# side.net
KiCad netlist of a schematic drawn in EAGLE
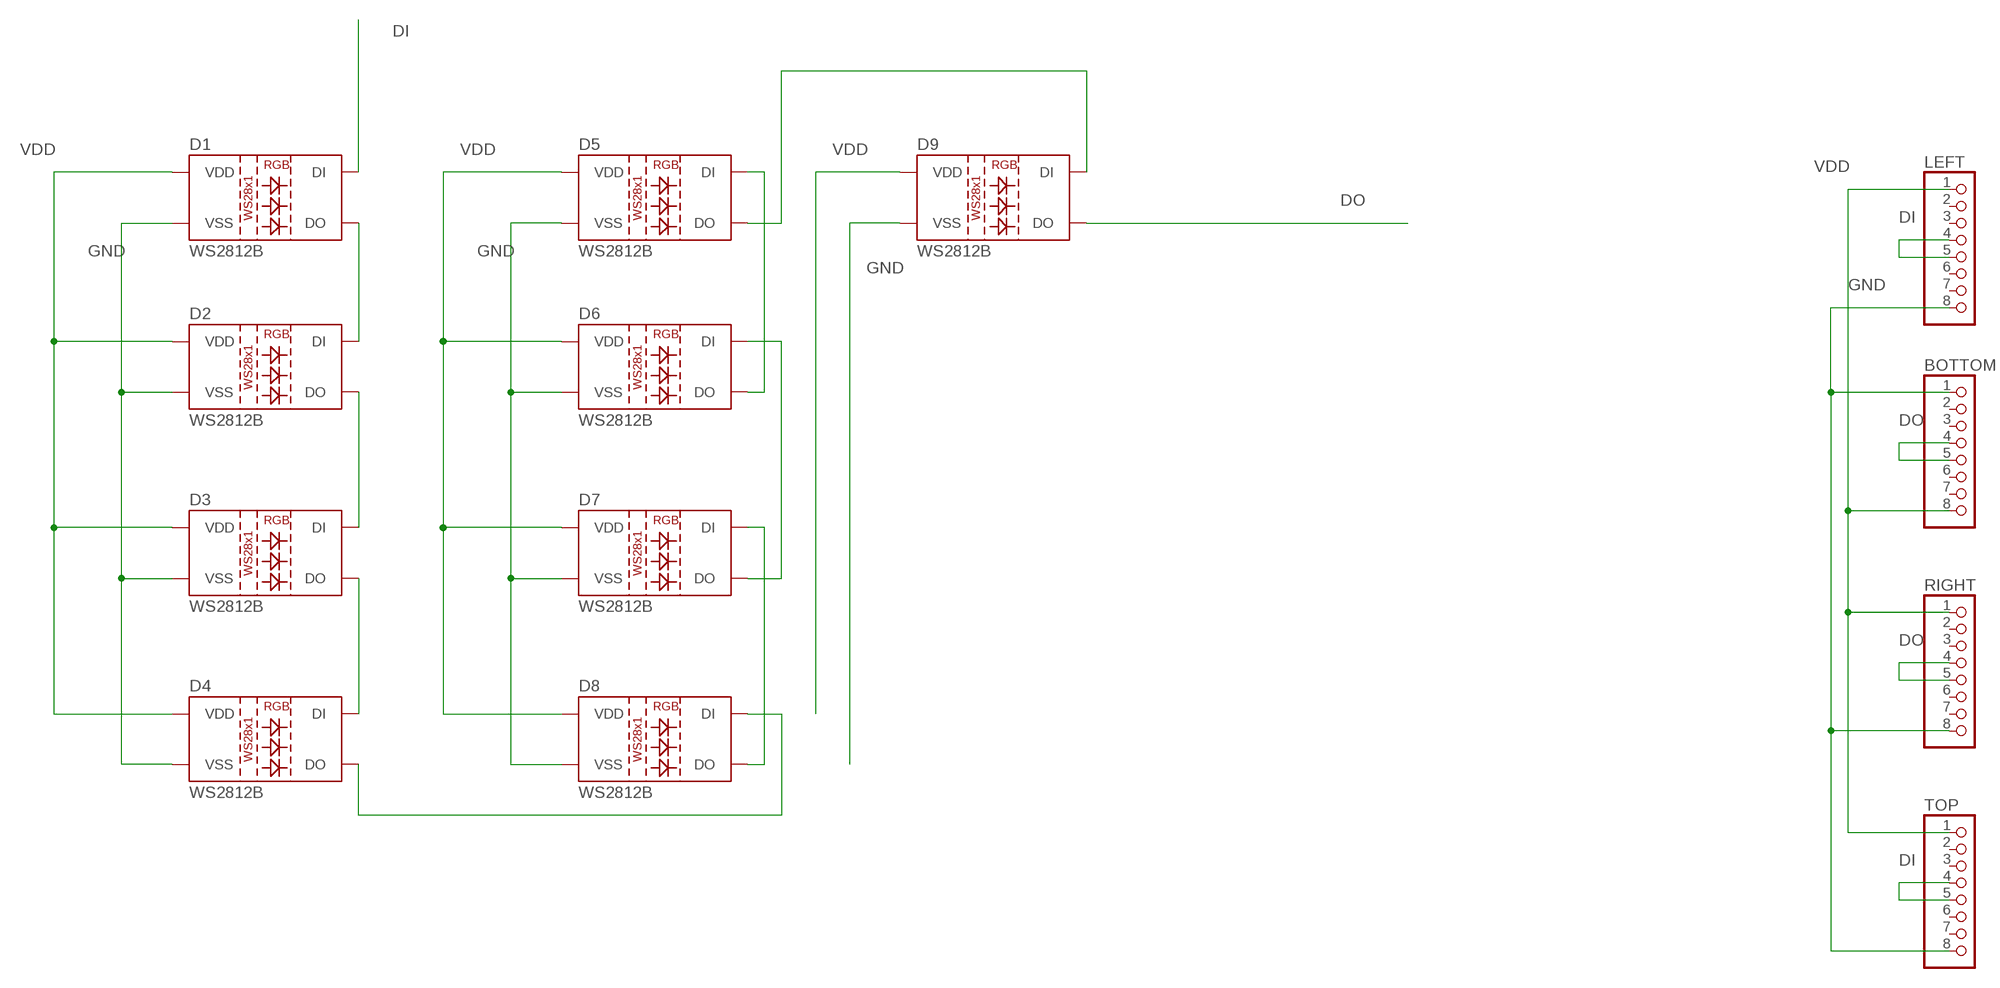
[diagram p0: schematic, sheet 1]

(export (version "E")
  (design (tool "Eeschema 10.0.6"))
  (components
    (comp (ref "BOTTOM")
      (value "PINHD-1X8")
      (footprint "eagle-import:1X08")
      (libsource (lib "eagle-import") (part "PINHD-1X8"))
    )
    (comp (ref "D1")
      (value "WS2812B")
      (footprint "eagle-import:WS2812B")
      (libsource (lib "eagle-import") (part "WS2812B"))
    )
    (comp (ref "D2")
      (value "WS2812B")
      (footprint "eagle-import:WS2812B")
      (libsource (lib "eagle-import") (part "WS2812B"))
    )
    (comp (ref "D3")
      (value "WS2812B")
      (footprint "eagle-import:WS2812B")
      (libsource (lib "eagle-import") (part "WS2812B"))
    )
    (comp (ref "D4")
      (value "WS2812B")
      (footprint "eagle-import:WS2812B")
      (libsource (lib "eagle-import") (part "WS2812B"))
    )
    (comp (ref "D5")
      (value "WS2812B")
      (footprint "eagle-import:WS2812B")
      (libsource (lib "eagle-import") (part "WS2812B"))
    )
    (comp (ref "D6")
      (value "WS2812B")
      (footprint "eagle-import:WS2812B")
      (libsource (lib "eagle-import") (part "WS2812B"))
    )
    (comp (ref "D7")
      (value "WS2812B")
      (footprint "eagle-import:WS2812B")
      (libsource (lib "eagle-import") (part "WS2812B"))
    )
    (comp (ref "D8")
      (value "WS2812B")
      (footprint "eagle-import:WS2812B")
      (libsource (lib "eagle-import") (part "WS2812B"))
    )
    (comp (ref "D9")
      (value "WS2812B")
      (footprint "eagle-import:WS2812B")
      (libsource (lib "eagle-import") (part "WS2812B"))
    )
    (comp (ref "LEFT")
      (value "PINHD-1X8")
      (footprint "eagle-import:1X08")
      (libsource (lib "eagle-import") (part "PINHD-1X8"))
    )
    (comp (ref "RIGHT")
      (value "PINHD-1X8")
      (footprint "eagle-import:1X08")
      (libsource (lib "eagle-import") (part "PINHD-1X8"))
    )
    (comp (ref "TOP")
      (value "PINHD-1X8")
      (footprint "eagle-import:1X08")
      (libsource (lib "eagle-import") (part "PINHD-1X8"))
    )
  )
  (nets
    (net (code "1") (name "/DI") (class "Default")
      (node (ref "D1") (pin "4") (pinfunction "DI_4") (pintype "bidirectional"))
      (node (ref "LEFT") (pin "4") (pinfunction "4_4") (pintype "passive"))
      (node (ref "LEFT") (pin "5") (pinfunction "5_5") (pintype "passive"))
      (node (ref "TOP") (pin "4") (pinfunction "4_4") (pintype "passive"))
      (node (ref "TOP") (pin "5") (pinfunction "5_5") (pintype "passive"))
    )
    (net (code "2") (name "/DO") (class "Default")
      (node (ref "BOTTOM") (pin "4") (pinfunction "4_4") (pintype "passive"))
      (node (ref "BOTTOM") (pin "5") (pinfunction "5_5") (pintype "passive"))
      (node (ref "D9") (pin "2") (pinfunction "DO_2") (pintype "bidirectional"))
      (node (ref "RIGHT") (pin "4") (pinfunction "4_4") (pintype "passive"))
      (node (ref "RIGHT") (pin "5") (pinfunction "5_5") (pintype "passive"))
    )
    (net (code "3") (name "/GND") (class "Default")
      (node (ref "BOTTOM") (pin "8") (pinfunction "8_8") (pintype "passive"))
      (node (ref "D1") (pin "3") (pinfunction "VSS_3") (pintype "bidirectional"))
      (node (ref "D2") (pin "3") (pinfunction "VSS_3") (pintype "bidirectional"))
      (node (ref "D3") (pin "3") (pinfunction "VSS_3") (pintype "bidirectional"))
      (node (ref "D4") (pin "3") (pinfunction "VSS_3") (pintype "bidirectional"))
      (node (ref "D5") (pin "3") (pinfunction "VSS_3") (pintype "bidirectional"))
      (node (ref "D6") (pin "3") (pinfunction "VSS_3") (pintype "bidirectional"))
      (node (ref "D7") (pin "3") (pinfunction "VSS_3") (pintype "bidirectional"))
      (node (ref "D8") (pin "3") (pinfunction "VSS_3") (pintype "bidirectional"))
      (node (ref "D9") (pin "3") (pinfunction "VSS_3") (pintype "bidirectional"))
      (node (ref "LEFT") (pin "1") (pinfunction "1_1") (pintype "passive"))
      (node (ref "RIGHT") (pin "1") (pinfunction "1_1") (pintype "passive"))
      (node (ref "TOP") (pin "1") (pinfunction "1_1") (pintype "passive"))
    )
    (net (code "4") (name "/VDD") (class "Default")
      (node (ref "BOTTOM") (pin "1") (pinfunction "1_1") (pintype "passive"))
      (node (ref "D1") (pin "1") (pinfunction "VDD_1") (pintype "bidirectional"))
      (node (ref "D2") (pin "1") (pinfunction "VDD_1") (pintype "bidirectional"))
      (node (ref "D3") (pin "1") (pinfunction "VDD_1") (pintype "bidirectional"))
      (node (ref "D4") (pin "1") (pinfunction "VDD_1") (pintype "bidirectional"))
      (node (ref "D5") (pin "1") (pinfunction "VDD_1") (pintype "bidirectional"))
      (node (ref "D6") (pin "1") (pinfunction "VDD_1") (pintype "bidirectional"))
      (node (ref "D7") (pin "1") (pinfunction "VDD_1") (pintype "bidirectional"))
      (node (ref "D8") (pin "1") (pinfunction "VDD_1") (pintype "bidirectional"))
      (node (ref "D9") (pin "1") (pinfunction "VDD_1") (pintype "bidirectional"))
      (node (ref "LEFT") (pin "8") (pinfunction "8_8") (pintype "passive"))
      (node (ref "RIGHT") (pin "8") (pinfunction "8_8") (pintype "passive"))
      (node (ref "TOP") (pin "8") (pinfunction "8_8") (pintype "passive"))
    )
    (net (code "5") (name "Net-(D1-DO)") (class "Default")
      (node (ref "D1") (pin "2") (pinfunction "DO_2") (pintype "bidirectional"))
      (node (ref "D2") (pin "4") (pinfunction "DI_4") (pintype "bidirectional"))
    )
    (net (code "6") (name "Net-(D2-DO)") (class "Default")
      (node (ref "D2") (pin "2") (pinfunction "DO_2") (pintype "bidirectional"))
      (node (ref "D3") (pin "4") (pinfunction "DI_4") (pintype "bidirectional"))
    )
    (net (code "7") (name "Net-(D3-DO)") (class "Default")
      (node (ref "D3") (pin "2") (pinfunction "DO_2") (pintype "bidirectional"))
      (node (ref "D4") (pin "4") (pinfunction "DI_4") (pintype "bidirectional"))
    )
    (net (code "8") (name "Net-(D4-DO)") (class "Default")
      (node (ref "D4") (pin "2") (pinfunction "DO_2") (pintype "bidirectional"))
      (node (ref "D8") (pin "4") (pinfunction "DI_4") (pintype "bidirectional"))
    )
    (net (code "9") (name "Net-(D5-DI)") (class "Default")
      (node (ref "D5") (pin "4") (pinfunction "DI_4") (pintype "bidirectional"))
      (node (ref "D6") (pin "2") (pinfunction "DO_2") (pintype "bidirectional"))
    )
    (net (code "10") (name "Net-(D5-DO)") (class "Default")
      (node (ref "D5") (pin "2") (pinfunction "DO_2") (pintype "bidirectional"))
      (node (ref "D9") (pin "4") (pinfunction "DI_4") (pintype "bidirectional"))
    )
    (net (code "11") (name "Net-(D6-DI)") (class "Default")
      (node (ref "D6") (pin "4") (pinfunction "DI_4") (pintype "bidirectional"))
      (node (ref "D7") (pin "2") (pinfunction "DO_2") (pintype "bidirectional"))
    )
    (net (code "12") (name "Net-(D7-DI)") (class "Default")
      (node (ref "D7") (pin "4") (pinfunction "DI_4") (pintype "bidirectional"))
      (node (ref "D8") (pin "2") (pinfunction "DO_2") (pintype "bidirectional"))
    )
    (net (code "13") (name "unconnected-(BOTTOM-Pad2)") (class "Default")
      (node (ref "BOTTOM") (pin "2") (pinfunction "2_2") (pintype "passive"))
    )
    (net (code "14") (name "unconnected-(BOTTOM-Pad3)") (class "Default")
      (node (ref "BOTTOM") (pin "3") (pinfunction "3_3") (pintype "passive"))
    )
    (net (code "15") (name "unconnected-(BOTTOM-Pad6)") (class "Default")
      (node (ref "BOTTOM") (pin "6") (pinfunction "6_6") (pintype "passive"))
    )
    (net (code "16") (name "unconnected-(BOTTOM-Pad7)") (class "Default")
      (node (ref "BOTTOM") (pin "7") (pinfunction "7_7") (pintype "passive"))
    )
    (net (code "17") (name "unconnected-(LEFT-Pad2)") (class "Default")
      (node (ref "LEFT") (pin "2") (pinfunction "2_2") (pintype "passive"))
    )
    (net (code "18") (name "unconnected-(LEFT-Pad3)") (class "Default")
      (node (ref "LEFT") (pin "3") (pinfunction "3_3") (pintype "passive"))
    )
    (net (code "19") (name "unconnected-(LEFT-Pad6)") (class "Default")
      (node (ref "LEFT") (pin "6") (pinfunction "6_6") (pintype "passive"))
    )
    (net (code "20") (name "unconnected-(LEFT-Pad7)") (class "Default")
      (node (ref "LEFT") (pin "7") (pinfunction "7_7") (pintype "passive"))
    )
    (net (code "21") (name "unconnected-(RIGHT-Pad2)") (class "Default")
      (node (ref "RIGHT") (pin "2") (pinfunction "2_2") (pintype "passive"))
    )
    (net (code "22") (name "unconnected-(RIGHT-Pad3)") (class "Default")
      (node (ref "RIGHT") (pin "3") (pinfunction "3_3") (pintype "passive"))
    )
    (net (code "23") (name "unconnected-(RIGHT-Pad6)") (class "Default")
      (node (ref "RIGHT") (pin "6") (pinfunction "6_6") (pintype "passive"))
    )
    (net (code "24") (name "unconnected-(RIGHT-Pad7)") (class "Default")
      (node (ref "RIGHT") (pin "7") (pinfunction "7_7") (pintype "passive"))
    )
    (net (code "25") (name "unconnected-(TOP-Pad2)") (class "Default")
      (node (ref "TOP") (pin "2") (pinfunction "2_2") (pintype "passive"))
    )
    (net (code "26") (name "unconnected-(TOP-Pad3)") (class "Default")
      (node (ref "TOP") (pin "3") (pinfunction "3_3") (pintype "passive"))
    )
    (net (code "27") (name "unconnected-(TOP-Pad6)") (class "Default")
      (node (ref "TOP") (pin "6") (pinfunction "6_6") (pintype "passive"))
    )
    (net (code "28") (name "unconnected-(TOP-Pad7)") (class "Default")
      (node (ref "TOP") (pin "7") (pinfunction "7_7") (pintype "passive"))
    )
  )
)
